# ADC-LOGIC_LEVEL_CONVERTERS.net
KiCad netlist of a schematic drawn in Altium Designer
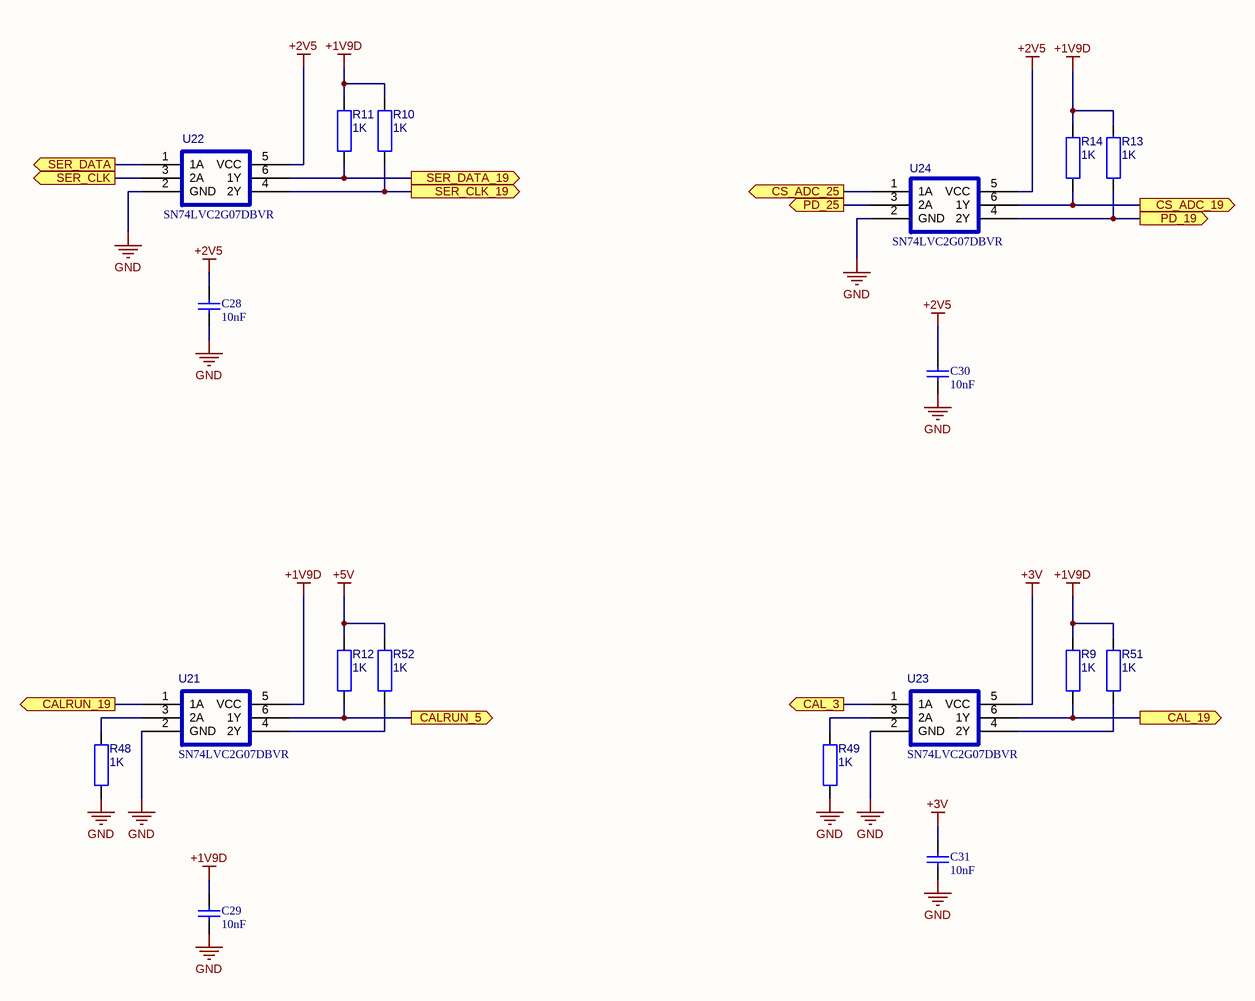
[diagram p0: ADC-LOGIC LEVEL CONVERTERS.SchDoc]

(export (version "E")
  (design (tool "Eeschema 10.0.6"))
  (components
    (comp (ref "C28")
      (value "10nF")
      (footprint "CAPC1005X55N")
      (description "Capacitor 0402 SMD")
      (fields (field (name "CREATED_BY") "EDA-ASA") (field (name "CHECKED_BY") "*"))
      (libsource (lib "EDA-Passive") (part "cap0402"))
    )
    (comp (ref "C29")
      (value "10nF")
      (footprint "CAPC1005X55N")
      (description "Capacitor 0402 SMD")
      (fields (field (name "CREATED_BY") "EDA-ASA") (field (name "CHECKED_BY") "*"))
      (libsource (lib "EDA-Passive") (part "cap0402"))
    )
    (comp (ref "C30")
      (value "10nF")
      (footprint "CAPC1005X55N")
      (description "Capacitor 0402 SMD")
      (fields (field (name "CREATED_BY") "EDA-ASA") (field (name "CHECKED_BY") "*"))
      (libsource (lib "EDA-Passive") (part "cap0402"))
    )
    (comp (ref "C31")
      (value "10nF")
      (footprint "CAPC1005X55N")
      (description "Capacitor 0402 SMD")
      (fields (field (name "CREATED_BY") "EDA-ASA") (field (name "CHECKED_BY") "*"))
      (libsource (lib "EDA-Passive") (part "cap0402"))
    )
    (comp (ref "R9")
      (value "1K")
      (footprint "0603")
      (description "RESISTOR SMD 0805")
      (fields (field (name "CREATED_BY") "*") (field (name "CHECKED_BY") "NN"))
      (libsource (lib "EDA_Passive") (part "RES-0805"))
    )
    (comp (ref "R10")
      (value "1K")
      (footprint "0603")
      (description "RESISTOR SMD 0805")
      (fields (field (name "CREATED_BY") "*") (field (name "CHECKED_BY") "NN"))
      (libsource (lib "EDA_Passive") (part "RES-0805"))
    )
    (comp (ref "R11")
      (value "1K")
      (footprint "0603")
      (description "RESISTOR SMD 0805")
      (fields (field (name "CREATED_BY") "*") (field (name "CHECKED_BY") "NN"))
      (libsource (lib "EDA_Passive") (part "RES-0805"))
    )
    (comp (ref "R12")
      (value "1K")
      (footprint "0603")
      (description "RESISTOR SMD 0805")
      (fields (field (name "CREATED_BY") "*") (field (name "CHECKED_BY") "NN"))
      (libsource (lib "EDA_Passive") (part "RES-0805"))
    )
    (comp (ref "R13")
      (value "1K")
      (footprint "0603")
      (description "RESISTOR SMD 0805")
      (fields (field (name "CREATED_BY") "*") (field (name "CHECKED_BY") "NN"))
      (libsource (lib "EDA_Passive") (part "RES-0805"))
    )
    (comp (ref "R14")
      (value "1K")
      (footprint "0603")
      (description "RESISTOR SMD 0805")
      (fields (field (name "CREATED_BY") "*") (field (name "CHECKED_BY") "NN"))
      (libsource (lib "EDA_Passive") (part "RES-0805"))
    )
    (comp (ref "R48")
      (value "1K")
      (footprint "0603")
      (description "RESISTOR SMD 0805")
      (fields (field (name "CREATED_BY") "*") (field (name "CHECKED_BY") "NN"))
      (libsource (lib "EDA_Passive") (part "RES-0805"))
    )
    (comp (ref "R49")
      (value "1K")
      (footprint "0603")
      (description "RESISTOR SMD 0805")
      (fields (field (name "CREATED_BY") "*") (field (name "CHECKED_BY") "NN"))
      (libsource (lib "EDA_Passive") (part "RES-0805"))
    )
    (comp (ref "R51")
      (value "1K")
      (footprint "0603")
      (description "RESISTOR SMD 0805")
      (fields (field (name "CREATED_BY") "*") (field (name "CHECKED_BY") "NN"))
      (libsource (lib "EDA_Passive") (part "RES-0805"))
    )
    (comp (ref "R52")
      (value "1K")
      (footprint "0603")
      (description "RESISTOR SMD 0805")
      (fields (field (name "CREATED_BY") "*") (field (name "CHECKED_BY") "NN"))
      (libsource (lib "EDA_Passive") (part "RES-0805"))
    )
    (comp (ref "U21")
      (value "SN74LVC2G07DBVR")
      (footprint "SOT95P280X145-6N")
      (description "Dual Buffer/Driver with open-drain output")
      (fields
        (field (name "MANUFACTURER") "TI")
        (field (name "CREATED_BY") "IN")
        (field (name "CHECKED_BY") "*")
      )
      (libsource (lib "Ishvah-TEMP") (part "SN74LVC2G07DBVR"))
    )
    (comp (ref "U22")
      (value "SN74LVC2G07DBVR")
      (footprint "SOT95P280X145-6N")
      (description "Dual Buffer/Driver with open-drain output")
      (fields
        (field (name "MANUFACTURER") "TI")
        (field (name "CREATED_BY") "IN")
        (field (name "CHECKED_BY") "*")
      )
      (libsource (lib "Ishvah-TEMP") (part "SN74LVC2G07DBVR"))
    )
    (comp (ref "U23")
      (value "SN74LVC2G07DBVR")
      (footprint "SOT95P280X145-6N")
      (description "Dual Buffer/Driver with open-drain output")
      (fields
        (field (name "MANUFACTURER") "TI")
        (field (name "CREATED_BY") "IN")
        (field (name "CHECKED_BY") "*")
      )
      (libsource (lib "Ishvah-TEMP") (part "SN74LVC2G07DBVR"))
    )
    (comp (ref "U24")
      (value "SN74LVC2G07DBVR")
      (footprint "SOT95P280X145-6N")
      (description "Dual Buffer/Driver with open-drain output")
      (fields
        (field (name "MANUFACTURER") "TI")
        (field (name "CREATED_BY") "IN")
        (field (name "CHECKED_BY") "*")
      )
      (libsource (lib "Ishvah-TEMP") (part "SN74LVC2G07DBVR"))
    )
  )
  (nets
    (net (code "1") (name "+1V9D") (class "Default")
      (node (ref "C29") (pin "2") (pinfunction "2_2") (pintype "passive"))
      (node (ref "R10") (pin "1") (pinfunction "1_1") (pintype "passive"))
      (node (ref "R11") (pin "1") (pinfunction "1_1") (pintype "passive"))
      (node (ref "R13") (pin "1") (pinfunction "1_1") (pintype "passive"))
      (node (ref "R14") (pin "1") (pinfunction "1_1") (pintype "passive"))
      (node (ref "R51") (pin "1") (pinfunction "1_1") (pintype "passive"))
      (node (ref "R9") (pin "1") (pinfunction "1_1") (pintype "passive"))
      (node (ref "U21") (pin "5") (pinfunction "VCC_5") (pintype "passive"))
    )
    (net (code "2") (name "+2V5") (class "Default")
      (node (ref "C28") (pin "2") (pinfunction "2_2") (pintype "passive"))
      (node (ref "C30") (pin "2") (pinfunction "2_2") (pintype "passive"))
      (node (ref "U22") (pin "5") (pinfunction "VCC_5") (pintype "passive"))
      (node (ref "U24") (pin "5") (pinfunction "VCC_5") (pintype "passive"))
    )
    (net (code "3") (name "+3V") (class "Default")
      (node (ref "C31") (pin "2") (pinfunction "2_2") (pintype "passive"))
      (node (ref "U23") (pin "5") (pinfunction "VCC_5") (pintype "passive"))
    )
    (net (code "4") (name "+5V") (class "Default")
      (node (ref "R12") (pin "1") (pinfunction "1_1") (pintype "passive"))
      (node (ref "R52") (pin "1") (pinfunction "1_1") (pintype "passive"))
    )
    (net (code "5") (name "/CALRUN_5") (class "Default")
      (node (ref "R12") (pin "2") (pinfunction "2_2") (pintype "passive"))
      (node (ref "U21") (pin "6") (pinfunction "1Y_6") (pintype "passive"))
    )
    (net (code "6") (name "/CALRUN_19") (class "Default")
      (node (ref "U21") (pin "1") (pinfunction "1A_1") (pintype "passive"))
    )
    (net (code "7") (name "/CAL_3") (class "Default")
      (node (ref "U23") (pin "1") (pinfunction "1A_1") (pintype "passive"))
    )
    (net (code "8") (name "/CAL_19") (class "Default")
      (node (ref "R9") (pin "2") (pinfunction "2_2") (pintype "passive"))
      (node (ref "U23") (pin "6") (pinfunction "1Y_6") (pintype "passive"))
    )
    (net (code "9") (name "/CS_ADC_19") (class "Default")
      (node (ref "R14") (pin "2") (pinfunction "2_2") (pintype "passive"))
      (node (ref "U24") (pin "6") (pinfunction "1Y_6") (pintype "passive"))
    )
    (net (code "10") (name "/CS_ADC_25") (class "Default")
      (node (ref "U24") (pin "1") (pinfunction "1A_1") (pintype "passive"))
    )
    (net (code "11") (name "/PD_19") (class "Default")
      (node (ref "R13") (pin "2") (pinfunction "2_2") (pintype "passive"))
      (node (ref "U24") (pin "4") (pinfunction "2Y_4") (pintype "passive"))
    )
    (net (code "12") (name "/PD_25") (class "Default")
      (node (ref "U24") (pin "3") (pinfunction "2A_3") (pintype "passive"))
    )
    (net (code "13") (name "/SER_CLK") (class "Default")
      (node (ref "U22") (pin "3") (pinfunction "2A_3") (pintype "passive"))
    )
    (net (code "14") (name "/SER_CLK_19") (class "Default")
      (node (ref "R10") (pin "2") (pinfunction "2_2") (pintype "passive"))
      (node (ref "U22") (pin "4") (pinfunction "2Y_4") (pintype "passive"))
    )
    (net (code "15") (name "/SER_DATA") (class "Default")
      (node (ref "U22") (pin "1") (pinfunction "1A_1") (pintype "passive"))
    )
    (net (code "16") (name "/SER_DATA_19") (class "Default")
      (node (ref "R11") (pin "2") (pinfunction "2_2") (pintype "passive"))
      (node (ref "U22") (pin "6") (pinfunction "1Y_6") (pintype "passive"))
    )
    (net (code "17") (name "GND") (class "Default")
      (node (ref "C28") (pin "1") (pinfunction "1_1") (pintype "passive"))
      (node (ref "C29") (pin "1") (pinfunction "1_1") (pintype "passive"))
      (node (ref "C30") (pin "1") (pinfunction "1_1") (pintype "passive"))
      (node (ref "C31") (pin "1") (pinfunction "1_1") (pintype "passive"))
      (node (ref "R48") (pin "2") (pinfunction "2_2") (pintype "passive"))
      (node (ref "R49") (pin "2") (pinfunction "2_2") (pintype "passive"))
      (node (ref "U21") (pin "2") (pinfunction "GND_2") (pintype "passive"))
      (node (ref "U22") (pin "2") (pinfunction "GND_2") (pintype "passive"))
      (node (ref "U23") (pin "2") (pinfunction "GND_2") (pintype "passive"))
      (node (ref "U24") (pin "2") (pinfunction "GND_2") (pintype "passive"))
    )
    (net (code "18") (name "Net-(U21-2A)") (class "Default")
      (node (ref "R48") (pin "1") (pinfunction "1_1") (pintype "passive"))
      (node (ref "U21") (pin "3") (pinfunction "2A_3") (pintype "passive"))
    )
    (net (code "19") (name "Net-(U21-2Y)") (class "Default")
      (node (ref "R52") (pin "2") (pinfunction "2_2") (pintype "passive"))
      (node (ref "U21") (pin "4") (pinfunction "2Y_4") (pintype "passive"))
    )
    (net (code "20") (name "Net-(U23-2A)") (class "Default")
      (node (ref "R49") (pin "1") (pinfunction "1_1") (pintype "passive"))
      (node (ref "U23") (pin "3") (pinfunction "2A_3") (pintype "passive"))
    )
    (net (code "21") (name "Net-(U23-2Y)") (class "Default")
      (node (ref "R51") (pin "2") (pinfunction "2_2") (pintype "passive"))
      (node (ref "U23") (pin "4") (pinfunction "2Y_4") (pintype "passive"))
    )
  )
)
